# harp_camera_controller.net
KiCad netlist of a schematic drawn in EAGLE
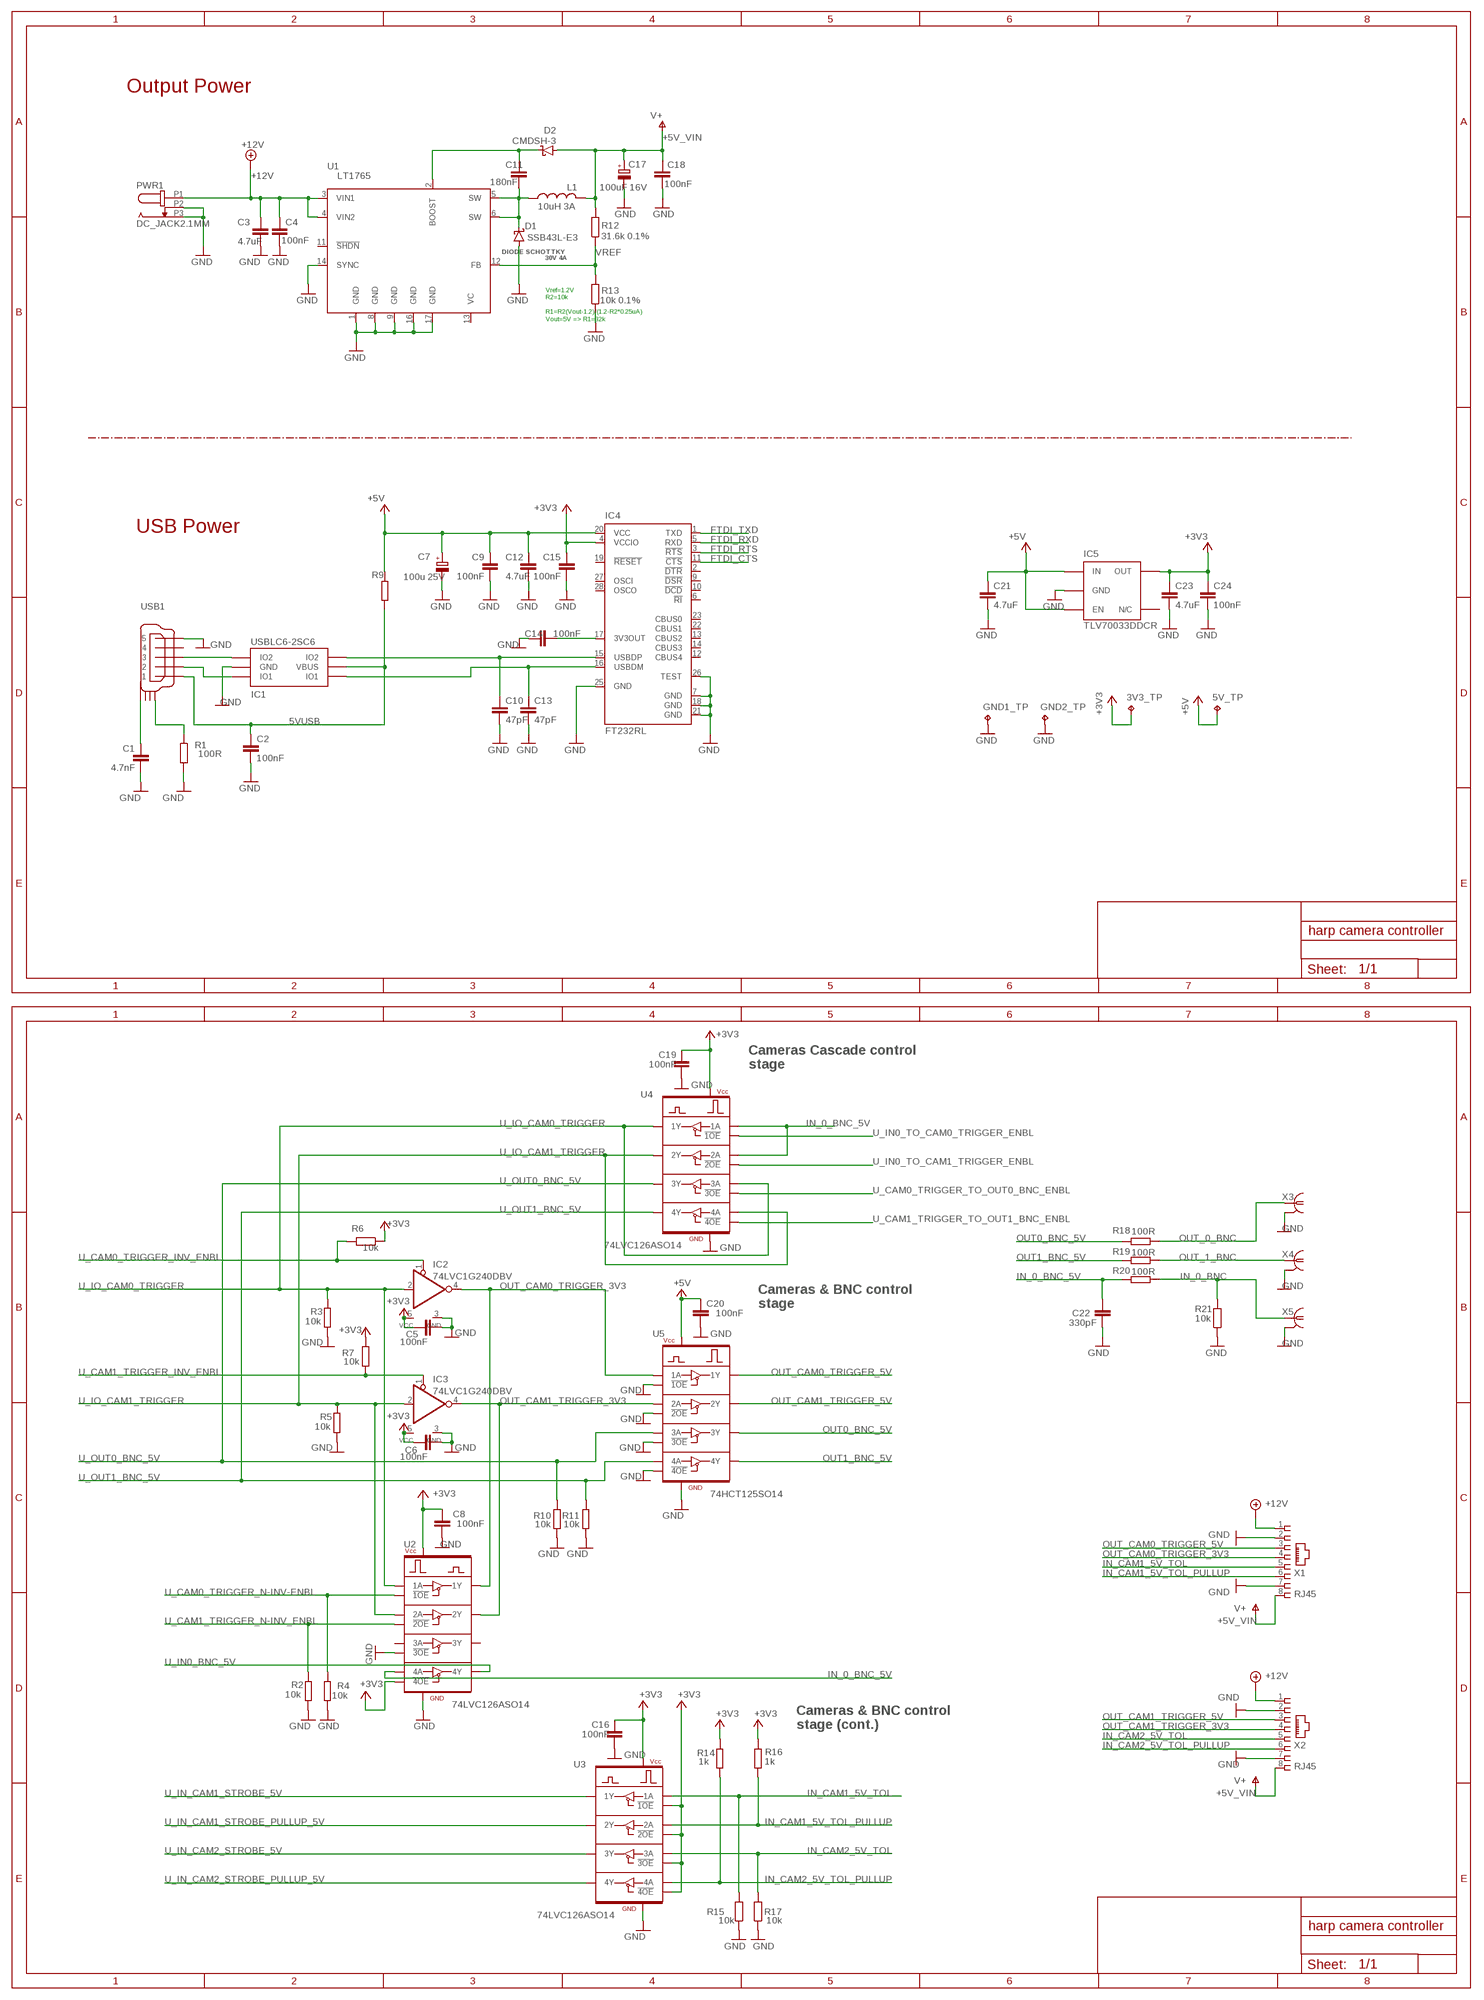
[diagram p0: schematic, sheet 1, part 1 of 2]
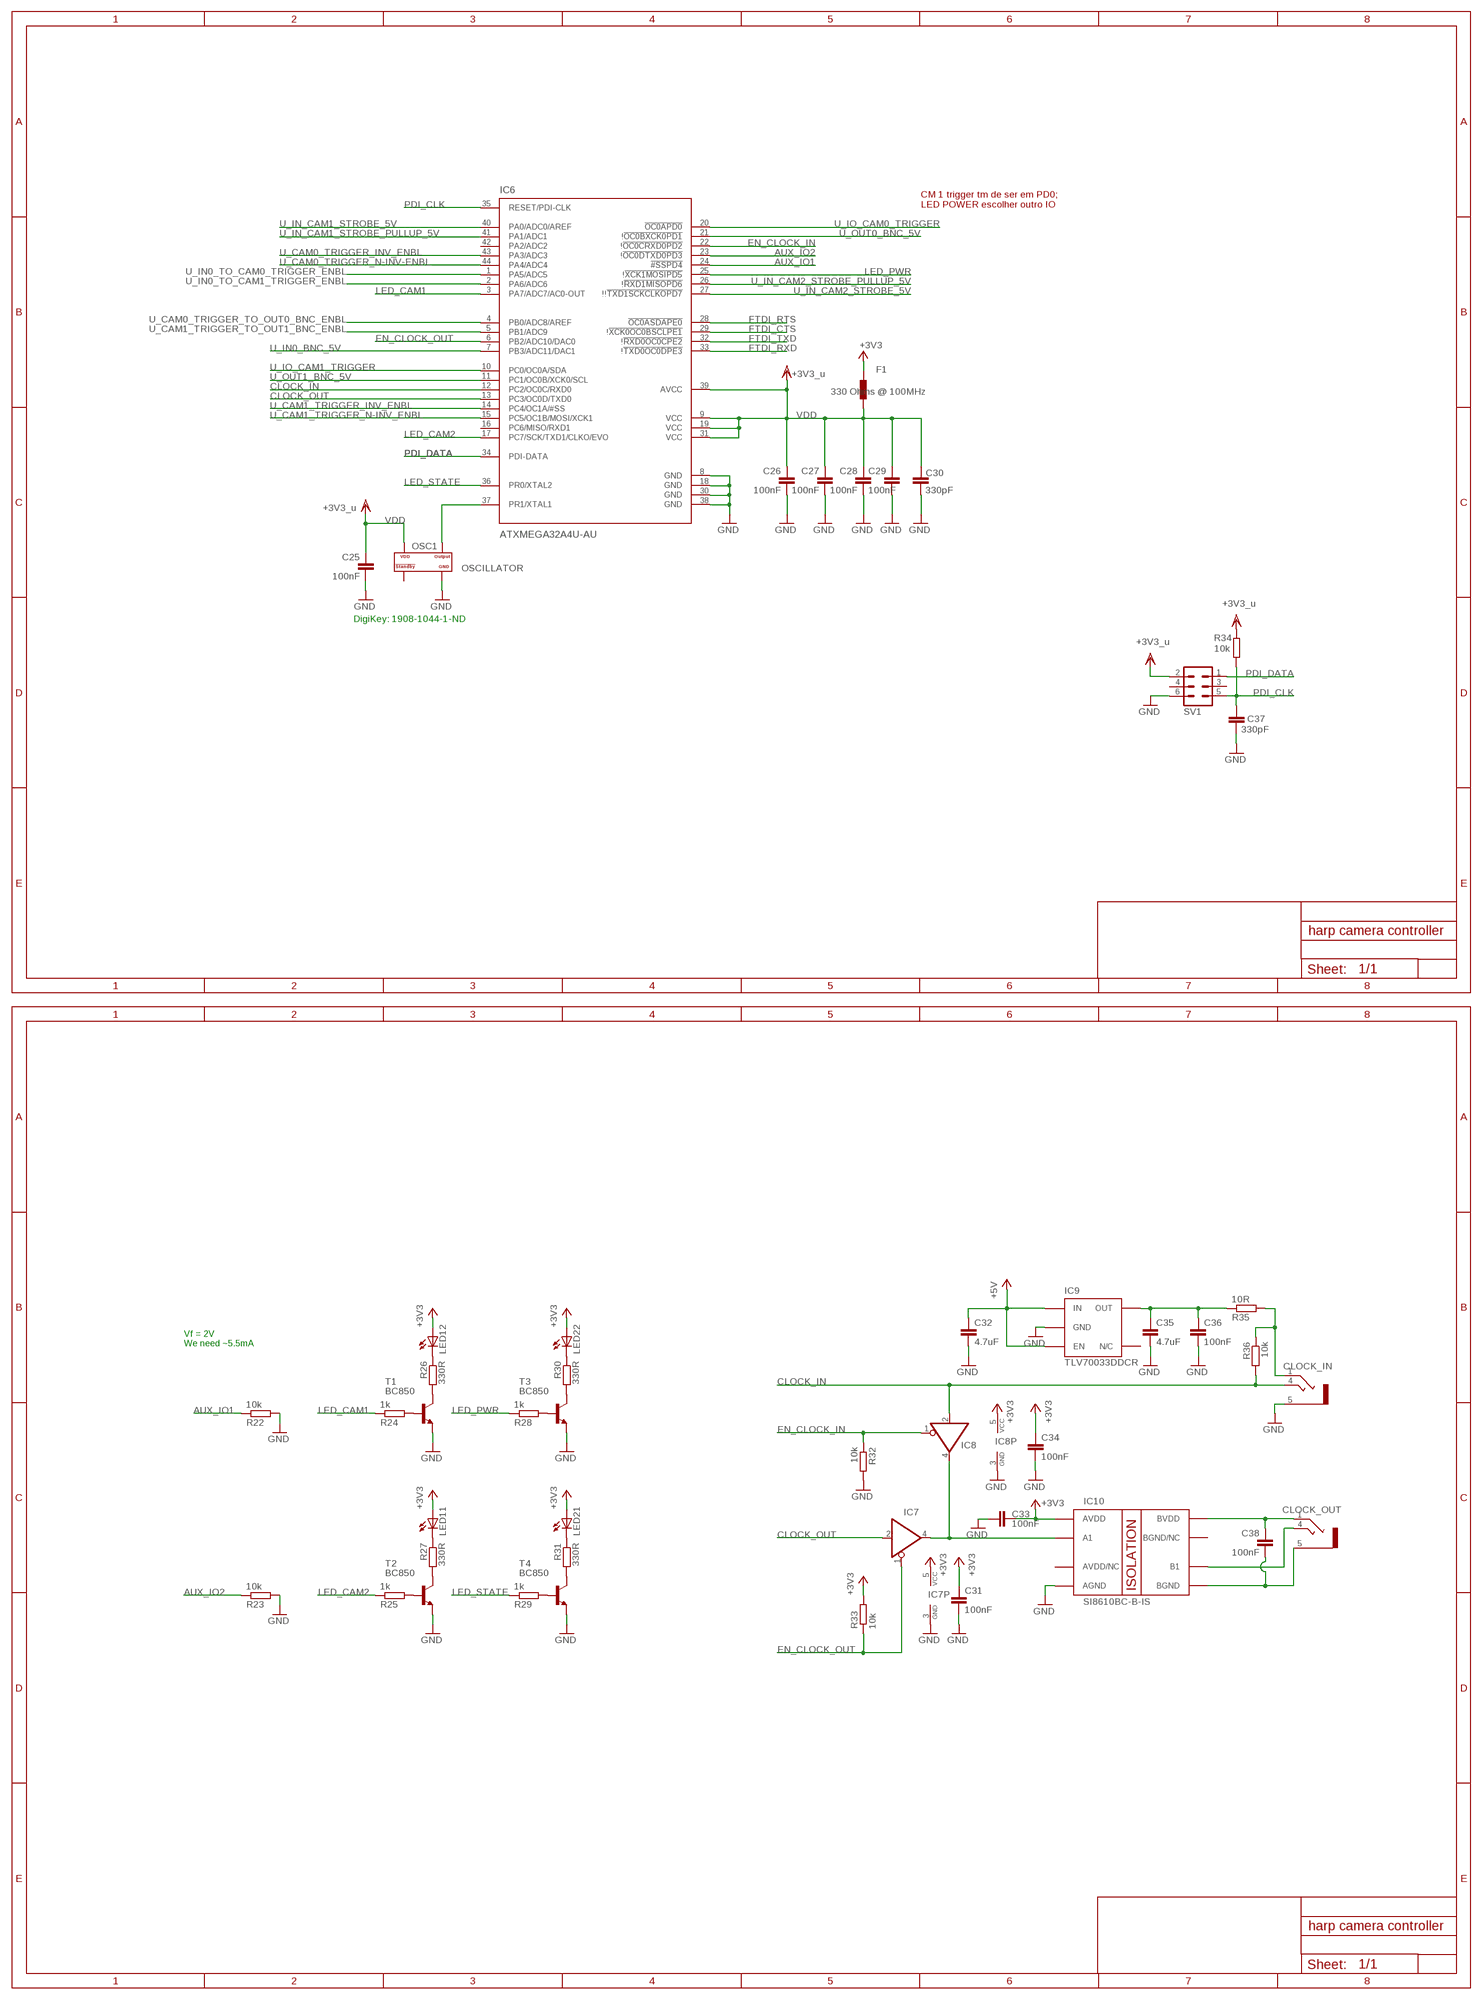
[diagram p1: schematic, sheet 1, part 2 of 2]

(export (version "E")
  (design (tool "Eeschema 10.0.6"))
  (components
    (comp (ref "3V3_TP")
      (value "TPPAD1-13")
      (footprint "eagle-import:P1-13")
      (fields (field (name "MPN") "N.A."))
      (libsource (lib "eagle-import") (part "TPPAD1-13"))
    )
    (comp (ref "5V_TP")
      (value "TPPAD1-13")
      (footprint "eagle-import:P1-13")
      (fields (field (name "MPN") "N.A."))
      (libsource (lib "eagle-import") (part "TPPAD1-13"))
    )
    (comp (ref "C1")
      (value "4.7nF")
      (footprint "eagle-import:C0402")
      (fields (field (name "MPN") "885012205084  "))
      (libsource (lib "eagle-import") (part "C-EUC0402"))
    )
    (comp (ref "C2")
      (value "100nF")
      (footprint "eagle-import:C0402")
      (fields (field (name "MPN") "C1005X7R1H104K050BB"))
      (libsource (lib "eagle-import") (part "C-EUC0402"))
    )
    (comp (ref "C3")
      (value "4.7uF")
      (footprint "eagle-import:C0805")
      (fields (field (name "MPN") "CL21A475KLCLQNC"))
      (libsource (lib "eagle-import") (part "C-EUC0805"))
    )
    (comp (ref "C4")
      (value "100nF")
      (footprint "eagle-import:C0402")
      (fields (field (name "MPN") "C1005X7R1H104K050BB"))
      (libsource (lib "eagle-import") (part "C-EUC0402"))
    )
    (comp (ref "C5")
      (value "100nF")
      (footprint "eagle-import:C0402")
      (fields (field (name "MPN") "C1005X7R1H104K050BB"))
      (libsource (lib "eagle-import") (part "C-EUC0402"))
    )
    (comp (ref "C6")
      (value "100nF")
      (footprint "eagle-import:C0402")
      (fields (field (name "MPN") "C1005X7R1H104K050BB"))
      (libsource (lib "eagle-import") (part "C-EUC0402"))
    )
    (comp (ref "C7")
      (value "100u 25V")
      (footprint "eagle-import:TT2D6")
      (fields (field (name "MPN") "EEU-FM1E101B"))
      (libsource (lib "eagle-import") (part "CPOL-EUTT2D6"))
    )
    (comp (ref "C8")
      (value "100nF")
      (footprint "eagle-import:C0402")
      (fields (field (name "MPN") "C1005X7R1H104K050BB"))
      (libsource (lib "eagle-import") (part "C-EUC0402"))
    )
    (comp (ref "C9")
      (value "100nF")
      (footprint "eagle-import:C0402")
      (fields (field (name "MPN") "C1005X7R1H104K050BB"))
      (libsource (lib "eagle-import") (part "C-EUC0402"))
    )
    (comp (ref "C10")
      (value "47pF")
      (footprint "eagle-import:C0402")
      (fields (field (name "MPN") "04025A470JAT2A"))
      (libsource (lib "eagle-import") (part "C-EUC0402"))
    )
    (comp (ref "C11")
      (value "180nF")
      (footprint "eagle-import:C0603")
      (fields (field (name "MPN") "GCG188R91H184KA01D"))
      (libsource (lib "eagle-import") (part "C-EUC0603"))
    )
    (comp (ref "C12")
      (value "4.7uF")
      (footprint "eagle-import:C0603")
      (fields (field (name "MPN") "C1608X6S1C475K080AC"))
      (libsource (lib "eagle-import") (part "C-EUC0603"))
    )
    (comp (ref "C13")
      (value "47pF")
      (footprint "eagle-import:C0402")
      (fields (field (name "MPN") "04025A470JAT2A"))
      (libsource (lib "eagle-import") (part "C-EUC0402"))
    )
    (comp (ref "C14")
      (value "100nF")
      (footprint "eagle-import:C0402")
      (fields (field (name "MPN") "C1005X7R1H104K050BB"))
      (libsource (lib "eagle-import") (part "C-EUC0402"))
    )
    (comp (ref "C15")
      (value "100nF")
      (footprint "eagle-import:C0402")
      (fields (field (name "MPN") "C1005X7R1H104K050BB"))
      (libsource (lib "eagle-import") (part "C-EUC0402"))
    )
    (comp (ref "C16")
      (value "100nF")
      (footprint "eagle-import:C0402")
      (fields (field (name "MPN") "C1005X7R1H104K050BB"))
      (libsource (lib "eagle-import") (part "C-EUC0402"))
    )
    (comp (ref "C17")
      (value "100uF 16V")
      (footprint "eagle-import:CT7343")
      (fields (field (name "MPN") "T491D107K016AT7280"))
      (libsource (lib "eagle-import") (part "CPOL-EUCT7343"))
    )
    (comp (ref "C18")
      (value "100nF")
      (footprint "eagle-import:C0402")
      (fields (field (name "MPN") "C1005X7R1H104K050BB"))
      (libsource (lib "eagle-import") (part "C-EUC0402"))
    )
    (comp (ref "C19")
      (value "100nF")
      (footprint "eagle-import:C0402")
      (fields (field (name "MPN") "C1005X7R1H104K050BB"))
      (libsource (lib "eagle-import") (part "C-EUC0402"))
    )
    (comp (ref "C20")
      (value "100nF")
      (footprint "eagle-import:C0402")
      (fields (field (name "MPN") "C1005X7R1H104K050BB"))
      (libsource (lib "eagle-import") (part "C-EUC0402"))
    )
    (comp (ref "C21")
      (value "4.7uF")
      (footprint "eagle-import:C0603")
      (fields (field (name "MPN") "C1608X6S1C475K080AC"))
      (libsource (lib "eagle-import") (part "C-EUC0603"))
    )
    (comp (ref "C22")
      (value "330pF")
      (footprint "eagle-import:C0402")
      (fields (field (name "MPN") "C0402C331J5GACTU"))
      (libsource (lib "eagle-import") (part "C-EUC0402"))
    )
    (comp (ref "C23")
      (value "4.7uF")
      (footprint "eagle-import:C0603")
      (fields (field (name "MPN") "C1608X6S1C475K080AC"))
      (libsource (lib "eagle-import") (part "C-EUC0603"))
    )
    (comp (ref "C24")
      (value "100nF")
      (footprint "eagle-import:C0402")
      (fields (field (name "MPN") "C1005X7R1H104K050BB"))
      (libsource (lib "eagle-import") (part "C-EUC0402"))
    )
    (comp (ref "C25")
      (value "100nF")
      (footprint "eagle-import:C0402")
      (fields (field (name "MPN") "C1005X7R1H104K050BB"))
      (libsource (lib "eagle-import") (part "C-EUC0402"))
    )
    (comp (ref "C26")
      (value "100nF")
      (footprint "eagle-import:C0402")
      (fields (field (name "MPN") "C1005X7R1H104K050BB"))
      (libsource (lib "eagle-import") (part "C-EUC0402"))
    )
    (comp (ref "C27")
      (value "100nF")
      (footprint "eagle-import:C0402")
      (fields (field (name "MPN") "C1005X7R1H104K050BB"))
      (libsource (lib "eagle-import") (part "C-EUC0402"))
    )
    (comp (ref "C28")
      (value "100nF")
      (footprint "eagle-import:C0402")
      (fields (field (name "MPN") "C1005X7R1H104K050BB"))
      (libsource (lib "eagle-import") (part "C-EUC0402"))
    )
    (comp (ref "C29")
      (value "100nF")
      (footprint "eagle-import:C0402")
      (fields (field (name "MPN") "C1005X7R1H104K050BB"))
      (libsource (lib "eagle-import") (part "C-EUC0402"))
    )
    (comp (ref "C30")
      (value "330pF")
      (footprint "eagle-import:C0402")
      (fields (field (name "MPN") "C0402C331J5GACTU"))
      (libsource (lib "eagle-import") (part "C-EUC0402"))
    )
    (comp (ref "C31")
      (value "100nF")
      (footprint "eagle-import:C0402")
      (fields (field (name "MPN") "C1005X7R1H104K050BB"))
      (libsource (lib "eagle-import") (part "C-EUC0402"))
    )
    (comp (ref "C32")
      (value "4.7uF")
      (footprint "eagle-import:C0603")
      (fields (field (name "MPN") "C1608X6S1C475K080AC"))
      (libsource (lib "eagle-import") (part "C-EUC0603"))
    )
    (comp (ref "C33")
      (value "100nF")
      (footprint "eagle-import:C0402")
      (fields (field (name "MPN") "C1005X7R1H104K050BB"))
      (libsource (lib "eagle-import") (part "C-EUC0402"))
    )
    (comp (ref "C34")
      (value "100nF")
      (footprint "eagle-import:C0402")
      (fields (field (name "MPN") "C1005X7R1H104K050BB"))
      (libsource (lib "eagle-import") (part "C-EUC0402"))
    )
    (comp (ref "C35")
      (value "4.7uF")
      (footprint "eagle-import:C0603")
      (fields (field (name "MPN") "C1608X6S1C475K080AC"))
      (libsource (lib "eagle-import") (part "C-EUC0603"))
    )
    (comp (ref "C36")
      (value "100nF")
      (footprint "eagle-import:C0402")
      (fields (field (name "MPN") "C1005X7R1H104K050BB"))
      (libsource (lib "eagle-import") (part "C-EUC0402"))
    )
    (comp (ref "C37")
      (value "330pF")
      (footprint "eagle-import:C0402")
      (fields (field (name "MPN") "C0402C331J5GACTU"))
      (libsource (lib "eagle-import") (part "C-EUC0402"))
    )
    (comp (ref "C38")
      (value "100nF")
      (footprint "eagle-import:C0402")
      (fields (field (name "MPN") "C1005X7R1H104K050BB"))
      (libsource (lib "eagle-import") (part "C-EUC0402"))
    )
    (comp (ref "CLOCK_IN")
      (value "CLCK_JACK")
      (footprint "eagle-import:35RASMT2BHNTRX")
      (fields (field (name "MPN") "35RASMT2BHNTRX"))
      (libsource (lib "eagle-import") (part "STEREO_JACK"))
    )
    (comp (ref "CLOCK_OUT")
      (value "CLCK_JACK")
      (footprint "eagle-import:35RASMT2BHNTRX")
      (fields (field (name "MPN") "35RASMT2BHNTRX"))
      (libsource (lib "eagle-import") (part "STEREO_JACK"))
    )
    (comp (ref "D1")
      (value "SSB43L-E3")
      (footprint "eagle-import:SMB")
      (fields (field (name "MPN") "SSB43L-E3/52T"))
      (libsource (lib "eagle-import") (part "SCHOTTKY-DIODE"))
    )
    (comp (ref "D2")
      (value "CMDSH-3")
      (footprint "eagle-import:SOD323-R")
      (libsource (lib "eagle-import") (part "SCHOTTKY-DIODESOD323"))
    )
    (comp (ref "F1")
      (value "330 Ohms @ 100MHz")
      (footprint "eagle-import:R0603")
      (fields (field (name "MPN") "BLM18SG331TN1D"))
      (libsource (lib "eagle-import") (part "BLM15HF0603"))
    )
    (comp (ref "GND1_TP")
      (value "TPPAD1-13")
      (footprint "eagle-import:P1-13")
      (fields (field (name "MPN") "N.A."))
      (libsource (lib "eagle-import") (part "TPPAD1-13"))
    )
    (comp (ref "GND2_TP")
      (value "TPPAD1-13")
      (footprint "eagle-import:P1-13")
      (fields (field (name "MPN") "N.A."))
      (libsource (lib "eagle-import") (part "TPPAD1-13"))
    )
    (comp (ref "IC1")
      (value "USBLC6-2SC6")
      (footprint "eagle-import:SOT23-6L")
      (libsource (lib "eagle-import") (part "USBLC6-2"))
    )
    (comp (ref "IC2")
      (value "74LVC1G240DBV")
      (footprint "eagle-import:SOT23-5")
      (fields (field (name "MPN") "SN74LVC1G240DBVR"))
      (libsource (lib "eagle-import") (part "74LVC1G240DBV"))
    )
    (comp (ref "IC3")
      (value "74LVC1G240DBV")
      (footprint "eagle-import:SOT23-5")
      (fields (field (name "MPN") "SN74LVC1G240DBVR"))
      (libsource (lib "eagle-import") (part "74LVC1G240DBV"))
    )
    (comp (ref "IC4")
      (value "FT232RL")
      (footprint "eagle-import:SSOP28")
      (fields (field (name "MPN") "FT232RL-REEL"))
      (libsource (lib "eagle-import") (part "FT232RL"))
    )
    (comp (ref "IC5")
      (value "TLV70033DDCR")
      (footprint "eagle-import:TSOT23-5")
      (libsource (lib "eagle-import") (part "TLV700XX"))
    )
    (comp (ref "IC6")
      (value "ATXMEGA32A4U-AU")
      (footprint "eagle-import:QFP80P1200X1200X120-44N")
      (fields (field (name "MPN") "ATXMEGA32A4U-AUR"))
      (libsource (lib "eagle-import") (part "AT-XMEGA-XXA4-AU"))
    )
    (comp (ref "IC7")
      (value "SN74LVC1G125DBVT")
      (footprint "eagle-import:SOT23-5")
      (fields
        (field (name "DIGIKEY_PN") "296-26595-1-ND")
        (field (name "MOUSER_PN") "595-SN74LVC1G125DBVT")
        (field (name "MPN") "SN74LVC1G125DBVT")
      )
      (libsource (lib "eagle-import") (part "741G125DBVAHC"))
    )
    (comp (ref "IC8")
      (value "SN74LVC1G125DBVT")
      (footprint "eagle-import:SOT23-5")
      (fields
        (field (name "DIGIKEY_PN") "296-26595-1-ND")
        (field (name "MOUSER_PN") "595-SN74LVC1G125DBVT")
        (field (name "MPN") "SN74LVC1G125DBVT")
      )
      (libsource (lib "eagle-import") (part "741G125DBVAHC"))
    )
    (comp (ref "IC9")
      (value "TLV70033DDCR")
      (footprint "eagle-import:TSOT23-5")
      (libsource (lib "eagle-import") (part "TLV700XX"))
    )
    (comp (ref "IC10")
      (value "SI8610BC-B-IS")
      (footprint "eagle-import:SO-08")
      (fields (field (name "MPN") "SI8610EC-B-IS"))
      (libsource (lib "eagle-import") (part "SI8610"))
    )
    (comp (ref "L1")
      (value "10uH 3A")
      (footprint "eagle-import:L_IHLP_PADS")
      (fields (field (name "MPN") "IHLP2525CZER100M01"))
      (libsource (lib "eagle-import") (part "L_IHLP2525CZER100M01"))
    )
    (comp (ref "LED1")
      (value "RED_LEDs")
      (footprint "eagle-import:569-011X-X00_LED_ARRAY")
      (fields (field (name "MPN") "5690-111-100F"))
      (libsource (lib "eagle-import") (part "LED_2X_VERTICAL"))
    )
    (comp (ref "LED2")
      (value "RED_LEDs")
      (footprint "eagle-import:569-011X-X00_LED_ARRAY")
      (fields (field (name "MPN") "5690-111-100F"))
      (libsource (lib "eagle-import") (part "LED_2X_VERTICAL"))
    )
    (comp (ref "OSC1")
      (value "OSCILLATOR")
      (footprint "eagle-import:OSCILLATOR_3.2X2.5")
      (fields (field (name "MPN") "O 32,0-JT32C-A-K-3,3-LF"))
      (libsource (lib "eagle-import") (part "OSCILLATOR"))
    )
    (comp (ref "PWR1")
      (value "DC_JACK2.1MM")
      (footprint "eagle-import:DC_POWER_INPUT_2.1MM")
      (fields (field (name "MPN") "163-179PH-EX"))
      (libsource (lib "eagle-import") (part "DC_JACK2.1MM"))
    )
    (comp (ref "R1")
      (value "100R")
      (footprint "eagle-import:R0603")
      (fields (field (name "MPN") "ERJ-3EKF1000V"))
      (libsource (lib "eagle-import") (part "R-EU_R0603"))
    )
    (comp (ref "R2")
      (value "10k")
      (footprint "eagle-import:R0402")
      (fields (field (name "MPN") "CRCW040210K0FKED"))
      (libsource (lib "eagle-import") (part "R-EU_R0402"))
    )
    (comp (ref "R3")
      (value "10k")
      (footprint "eagle-import:R0402")
      (fields (field (name "MPN") "CRCW040210K0FKED"))
      (libsource (lib "eagle-import") (part "R-EU_R0402"))
    )
    (comp (ref "R4")
      (value "10k")
      (footprint "eagle-import:R0402")
      (fields (field (name "MPN") "CRCW040210K0FKED"))
      (libsource (lib "eagle-import") (part "R-EU_R0402"))
    )
    (comp (ref "R5")
      (value "10k")
      (footprint "eagle-import:R0402")
      (fields (field (name "MPN") "CRCW040210K0FKED"))
      (libsource (lib "eagle-import") (part "R-EU_R0402"))
    )
    (comp (ref "R6")
      (value "10k")
      (footprint "eagle-import:R0402")
      (fields (field (name "MPN") "CRCW040210K0FKED"))
      (libsource (lib "eagle-import") (part "R-EU_R0402"))
    )
    (comp (ref "R7")
      (value "10k")
      (footprint "eagle-import:R0402")
      (fields (field (name "MPN") "CRCW040210K0FKED"))
      (libsource (lib "eagle-import") (part "R-EU_R0402"))
    )
    (comp (ref "R9")
      (value "40R@100MHz")
      (footprint "eagle-import:R0805")
      (fields (field (name "MPN") "MI0805K400R-10"))
      (libsource (lib "eagle-import") (part "R-EU_R0805"))
    )
    (comp (ref "R10")
      (value "10k")
      (footprint "eagle-import:R0402")
      (fields (field (name "MPN") "CRCW040210K0FKED"))
      (libsource (lib "eagle-import") (part "R-EU_R0402"))
    )
    (comp (ref "R11")
      (value "10k")
      (footprint "eagle-import:R0402")
      (fields (field (name "MPN") "CRCW040210K0FKED"))
      (libsource (lib "eagle-import") (part "R-EU_R0402"))
    )
    (comp (ref "R12")
      (value "31.6k 0.1%")
      (footprint "eagle-import:R0402")
      (fields (field (name "MPN") "RC0402FR-0740K2L"))
      (libsource (lib "eagle-import") (part "R-EU_R0402"))
    )
    (comp (ref "R13")
      (value "10k 0.1%")
      (footprint "eagle-import:R0402")
      (fields (field (name "MPN") "CRCW040210K0FKED"))
      (libsource (lib "eagle-import") (part "R-EU_R0402"))
    )
    (comp (ref "R14")
      (value "1k")
      (footprint "eagle-import:R0402")
      (fields (field (name "MPN") "CRCW04021K00FKEDC"))
      (libsource (lib "eagle-import") (part "R-EU_R0402"))
    )
    (comp (ref "R15")
      (value "10k")
      (footprint "eagle-import:R0402")
      (fields (field (name "MPN") "CRCW040210K0FKED"))
      (libsource (lib "eagle-import") (part "R-EU_R0402"))
    )
    (comp (ref "R16")
      (value "1k")
      (footprint "eagle-import:R0402")
      (fields (field (name "MPN") "CRCW04021K00FKEDC"))
      (libsource (lib "eagle-import") (part "R-EU_R0402"))
    )
    (comp (ref "R17")
      (value "10k")
      (footprint "eagle-import:R0402")
      (fields (field (name "MPN") "CRCW040210K0FKED"))
      (libsource (lib "eagle-import") (part "R-EU_R0402"))
    )
    (comp (ref "R18")
      (value "100R")
      (footprint "eagle-import:R0603")
      (fields (field (name "MPN") "ERJ-3EKF1000V"))
      (libsource (lib "eagle-import") (part "R-EU_R0603"))
    )
    (comp (ref "R19")
      (value "100R")
      (footprint "eagle-import:R0603")
      (fields (field (name "MPN") "ERJ-3EKF1000V"))
      (libsource (lib "eagle-import") (part "R-EU_R0603"))
    )
    (comp (ref "R20")
      (value "100R")
      (footprint "eagle-import:R0603")
      (fields (field (name "MPN") "ERJ-3EKF1000V"))
      (libsource (lib "eagle-import") (part "R-EU_R0603"))
    )
    (comp (ref "R21")
      (value "10k")
      (footprint "eagle-import:R0402")
      (fields (field (name "MPN") "CRCW040210K0FKED"))
      (libsource (lib "eagle-import") (part "R-EU_R0402"))
    )
    (comp (ref "R22")
      (value "10k")
      (footprint "eagle-import:R0402")
      (fields (field (name "MPN") "CRCW040210K0FKED"))
      (libsource (lib "eagle-import") (part "R-EU_R0402"))
    )
    (comp (ref "R23")
      (value "10k")
      (footprint "eagle-import:R0402")
      (fields (field (name "MPN") "CRCW040210K0FKED"))
      (libsource (lib "eagle-import") (part "R-EU_R0402"))
    )
    (comp (ref "R24")
      (value "1k")
      (footprint "eagle-import:R0402")
      (fields (field (name "MPN") "CRCW04021K00FKEDC"))
      (libsource (lib "eagle-import") (part "R-EU_R0402"))
    )
    (comp (ref "R25")
      (value "1k")
      (footprint "eagle-import:R0402")
      (fields (field (name "MPN") "CRCW04021K00FKEDC"))
      (libsource (lib "eagle-import") (part "R-EU_R0402"))
    )
    (comp (ref "R26")
      (value "330R")
      (footprint "eagle-import:R0402")
      (fields (field (name "MPN") "RC0402FR-07330RL "))
      (libsource (lib "eagle-import") (part "R-EU_R0402"))
    )
    (comp (ref "R27")
      (value "330R")
      (footprint "eagle-import:R0402")
      (fields (field (name "MPN") "RC0402FR-07330RL "))
      (libsource (lib "eagle-import") (part "R-EU_R0402"))
    )
    (comp (ref "R28")
      (value "1k")
      (footprint "eagle-import:R0402")
      (fields (field (name "MPN") "CRCW04021K00FKEDC"))
      (libsource (lib "eagle-import") (part "R-EU_R0402"))
    )
    (comp (ref "R29")
      (value "1k")
      (footprint "eagle-import:R0402")
      (fields (field (name "MPN") "CRCW04021K00FKEDC"))
      (libsource (lib "eagle-import") (part "R-EU_R0402"))
    )
    (comp (ref "R30")
      (value "330R")
      (footprint "eagle-import:R0402")
      (fields (field (name "MPN") "RC0402FR-07330RL "))
      (libsource (lib "eagle-import") (part "R-EU_R0402"))
    )
    (comp (ref "R31")
      (value "330R")
      (footprint "eagle-import:R0402")
      (fields (field (name "MPN") "RC0402FR-07330RL "))
      (libsource (lib "eagle-import") (part "R-EU_R0402"))
    )
    (comp (ref "R32")
      (value "10k")
      (footprint "eagle-import:R0402")
      (fields (field (name "MPN") "CRCW040210K0FKED"))
      (libsource (lib "eagle-import") (part "R-EU_R0402"))
    )
    (comp (ref "R33")
      (value "10k")
      (footprint "eagle-import:R0402")
      (fields (field (name "MPN") "CRCW040210K0FKED"))
      (libsource (lib "eagle-import") (part "R-EU_R0402"))
    )
    (comp (ref "R34")
      (value "10k")
      (footprint "eagle-import:R0402")
      (fields (field (name "MPN") "CRCW040210K0FKED"))
      (libsource (lib "eagle-import") (part "R-EU_R0402"))
    )
    (comp (ref "R35")
      (value "10R")
      (footprint "eagle-import:R0402")
      (fields (field (name "MPN") "CRCW040210R0FKEDC"))
      (libsource (lib "eagle-import") (part "R-EU_R0402"))
    )
    (comp (ref "R36")
      (value "10k")
      (footprint "eagle-import:R0402")
      (fields (field (name "MPN") "CRCW040210K0FKED"))
      (libsource (lib "eagle-import") (part "R-EU_R0402"))
    )
    (comp (ref "SV1")
      (value "PROG HEADER")
      (footprint "eagle-import:MA03-2")
      (fields (field (name "MPN") "61300621121"))
      (libsource (lib "eagle-import") (part "MA03-2"))
    )
    (comp (ref "T1")
      (value "BC850")
      (footprint "eagle-import:SOT23")
      (fields (field (name "MPN") "BC850C,215"))
      (libsource (lib "eagle-import") (part "BC850"))
    )
    (comp (ref "T2")
      (value "BC850")
      (footprint "eagle-import:SOT23")
      (fields (field (name "MPN") "BC850C,215"))
      (libsource (lib "eagle-import") (part "BC850"))
    )
    (comp (ref "T3")
      (value "BC850")
      (footprint "eagle-import:SOT23")
      (fields (field (name "MPN") "BC850C,215"))
      (libsource (lib "eagle-import") (part "BC850"))
    )
    (comp (ref "T4")
      (value "BC850")
      (footprint "eagle-import:SOT23")
      (fields (field (name "MPN") "BC850C,215"))
      (libsource (lib "eagle-import") (part "BC850"))
    )
    (comp (ref "U1")
      (value "LT1765")
      (footprint "eagle-import:TSSOP16EXP")
      (fields (field (name "MPN") "LT1765EFE#PBF"))
      (libsource (lib "eagle-import") (part "LT1765"))
    )
    (comp (ref "U2")
      (value "74LVC126ASO14")
      (footprint "eagle-import:SO14")
      (fields (field (name "MPN") "74LVC126AD,118  "))
      (libsource (lib "eagle-import") (part "74LVC126ASO14"))
    )
    (comp (ref "U3")
      (value "74LVC126ASO14")
      (footprint "eagle-import:SO14")
      (fields (field (name "MPN") "74LVC126AD,118  "))
      (libsource (lib "eagle-import") (part "74LVC126ASO14"))
    )
    (comp (ref "U4")
      (value "74LVC126ASO14")
      (footprint "eagle-import:SO14")
      (fields (field (name "MPN") "74LVC126AD,118  "))
      (libsource (lib "eagle-import") (part "74LVC126ASO14"))
    )
    (comp (ref "U5")
      (value "74HCT125SO14")
      (footprint "eagle-import:SO14")
      (fields (field (name "MPN") "74HCT125D,653"))
      (libsource (lib "eagle-import") (part "74HCT125SO14"))
    )
    (comp (ref "USB1")
      (value "mini USB")
      (footprint "eagle-import:240-0002-1")
      (fields (field (name "MPN") "UX60-MB-5S8 "))
      (libsource (lib "eagle-import") (part "USB_MINI_B"))
    )
    (comp (ref "X1")
      (value "RJ45")
      (footprint "eagle-import:RJ45-NO-SHIELD")
      (fields (field (name "MPN") "215877-1"))
      (libsource (lib "eagle-import") (part "RJ45"))
    )
    (comp (ref "X2")
      (value "RJ45")
      (footprint "eagle-import:RJ45-NO-SHIELD")
      (fields (field (name "MPN") "215877-1"))
      (libsource (lib "eagle-import") (part "RJ45"))
    )
    (comp (ref "X3")
      (value "BNC plug")
      (footprint "eagle-import:0731000105")
      (fields (field (name "MPN") "73100-0105"))
      (libsource (lib "eagle-import") (part "BNC_0731000105"))
    )
    (comp (ref "X4")
      (value "BNC plug")
      (footprint "eagle-import:0731000105")
      (fields (field (name "MPN") "73100-0105"))
      (libsource (lib "eagle-import") (part "BNC_0731000105"))
    )
    (comp (ref "X5")
      (value "BNC plug")
      (footprint "eagle-import:0731000105")
      (fields (field (name "MPN") "73100-0105"))
      (libsource (lib "eagle-import") (part "BNC_0731000105"))
    )
  )
  (nets
    (net (code "1") (name "+3V3") (class "Default")
      (node (ref "3V3_TP") (pin "TP") (pinfunction "TP_TP") (pintype "input"))
      (node (ref "C15") (pin "1") (pinfunction "1_1") (pintype "passive"))
      (node (ref "C16") (pin "1") (pinfunction "1_1") (pintype "passive"))
      (node (ref "C19") (pin "1") (pinfunction "1_1") (pintype "passive"))
      (node (ref "C23") (pin "1") (pinfunction "1_1") (pintype "passive"))
      (node (ref "C24") (pin "1") (pinfunction "1_1") (pintype "passive"))
      (node (ref "C31") (pin "1") (pinfunction "1_1") (pintype "passive"))
      (node (ref "C33") (pin "1") (pinfunction "1_1") (pintype "passive"))
      (node (ref "C34") (pin "1") (pinfunction "1_1") (pintype "passive"))
      (node (ref "C5") (pin "1") (pinfunction "1_1") (pintype "passive"))
      (node (ref "C6") (pin "1") (pinfunction "1_1") (pintype "passive"))
      (node (ref "C8") (pin "1") (pinfunction "1_1") (pintype "passive"))
      (node (ref "F1") (pin "2") (pinfunction "2_2") (pintype "passive"))
      (node (ref "IC10") (pin "1") (pinfunction "AVDD_1") (pintype "bidirectional"))
      (node (ref "IC2") (pin "5") (pinfunction "VCC_5") (pintype "input"))
      (node (ref "IC3") (pin "5") (pinfunction "VCC_5") (pintype "input"))
      (node (ref "IC4") (pin "4") (pinfunction "VCCIO_4") (pintype "input"))
      (node (ref "IC5") (pin "5") (pinfunction "OUT_5") (pintype "bidirectional"))
      (node (ref "IC7") (pin "5") (pinfunction "VCC_5") (pintype "power_in"))
      (node (ref "IC8") (pin "5") (pinfunction "VCC_5") (pintype "power_in"))
      (node (ref "LED1") (pin "A1") (pinfunction "A_A1") (pintype "passive"))
      (node (ref "LED1") (pin "A2") (pinfunction "A_A2") (pintype "passive"))
      (node (ref "LED2") (pin "A1") (pinfunction "A_A1") (pintype "passive"))
      (node (ref "LED2") (pin "A2") (pinfunction "A_A2") (pintype "passive"))
      (node (ref "R14") (pin "1") (pinfunction "1_1") (pintype "passive"))
      (node (ref "R16") (pin "1") (pinfunction "1_1") (pintype "passive"))
      (node (ref "R33") (pin "2") (pinfunction "2_2") (pintype "passive"))
      (node (ref "R6") (pin "1") (pinfunction "1_1") (pintype "passive"))
      (node (ref "R7") (pin "1") (pinfunction "1_1") (pintype "passive"))
      (node (ref "U2") (pin "13") (pinfunction "~{4OE}_13") (pintype "bidirectional"))
      (node (ref "U2") (pin "14") (pinfunction "VCC_14") (pintype "input"))
      (node (ref "U3") (pin "1") (pinfunction "~{1OE}_1") (pintype "bidirectional"))
      (node (ref "U3") (pin "10") (pinfunction "~{3OE}_10") (pintype "bidirectional"))
      (node (ref "U3") (pin "13") (pinfunction "~{4OE}_13") (pintype "bidirectional"))
      (node (ref "U3") (pin "14") (pinfunction "VCC_14") (pintype "input"))
      (node (ref "U3") (pin "4") (pinfunction "~{2OE}_4") (pintype "bidirectional"))
      (node (ref "U4") (pin "14") (pinfunction "VCC_14") (pintype "input"))
    )
    (net (code "2") (name "+3V3_u") (class "Default")
      (node (ref "C25") (pin "1") (pinfunction "1_1") (pintype "passive"))
      (node (ref "C26") (pin "1") (pinfunction "1_1") (pintype "passive"))
      (node (ref "C27") (pin "1") (pinfunction "1_1") (pintype "passive"))
      (node (ref "C28") (pin "1") (pinfunction "1_1") (pintype "passive"))
      (node (ref "C29") (pin "1") (pinfunction "1_1") (pintype "passive"))
      (node (ref "C30") (pin "1") (pinfunction "1_1") (pintype "passive"))
      (node (ref "F1") (pin "1") (pinfunction "1_1") (pintype "passive"))
      (node (ref "IC6") (pin "19") (pinfunction "VCC_19") (pintype "power_in"))
      (node (ref "IC6") (pin "31") (pinfunction "VCC_31") (pintype "power_in"))
      (node (ref "IC6") (pin "39") (pinfunction "AVCC_39") (pintype "power_in"))
      (node (ref "IC6") (pin "9") (pinfunction "VCC_9") (pintype "power_in"))
      (node (ref "OSC1") (pin "P$4") (pinfunction "VDD_P$4") (pintype "passive"))
      (node (ref "R34") (pin "2") (pinfunction "2_2") (pintype "passive"))
      (node (ref "SV1") (pin "2") (pinfunction "2_2") (pintype "passive"))
    )
    (net (code "3") (name "+5V") (class "Default")
      (node (ref "5V_TP") (pin "TP") (pinfunction "TP_TP") (pintype "input"))
      (node (ref "C12") (pin "1") (pinfunction "1_1") (pintype "passive"))
      (node (ref "C20") (pin "1") (pinfunction "1_1") (pintype "passive"))
      (node (ref "C21") (pin "1") (pinfunction "1_1") (pintype "passive"))
      (node (ref "C32") (pin "1") (pinfunction "1_1") (pintype "passive"))
      (node (ref "C7") (pin "+") (pinfunction "+_+") (pintype "passive"))
      (node (ref "C9") (pin "1") (pinfunction "1_1") (pintype "passive"))
      (node (ref "IC4") (pin "20") (pinfunction "VCC_20") (pintype "input"))
      (node (ref "IC5") (pin "1") (pinfunction "IN_1") (pintype "bidirectional"))
      (node (ref "IC5") (pin "3") (pinfunction "EN_3") (pintype "bidirectional"))
      (node (ref "IC9") (pin "1") (pinfunction "IN_1") (pintype "bidirectional"))
      (node (ref "IC9") (pin "3") (pinfunction "EN_3") (pintype "bidirectional"))
      (node (ref "R9") (pin "1") (pinfunction "1_1") (pintype "passive"))
      (node (ref "U5") (pin "14") (pinfunction "VCC_14") (pintype "input"))
    )
    (net (code "4") (name "+12V") (class "Default")
      (node (ref "C3") (pin "1") (pinfunction "1_1") (pintype "passive"))
      (node (ref "C4") (pin "1") (pinfunction "1_1") (pintype "passive"))
      (node (ref "PWR1") (pin "P1") (pinfunction "1_P1") (pintype "passive"))
      (node (ref "U1") (pin "3") (pinfunction "VIN1_3") (pintype "bidirectional"))
      (node (ref "U1") (pin "4") (pinfunction "VIN2_4") (pintype "bidirectional"))
      (node (ref "X1") (pin "1") (pinfunction "1_1") (pintype "passive"))
      (node (ref "X2") (pin "1") (pinfunction "1_1") (pintype "passive"))
    )
    (net (code "5") (name "/5VUSB") (class "Default")
      (node (ref "C2") (pin "1") (pinfunction "1_1") (pintype "passive"))
      (node (ref "IC1") (pin "P$5") (pinfunction "VBUS_P$5") (pintype "bidirectional"))
      (node (ref "R9") (pin "2") (pinfunction "2_2") (pintype "passive"))
      (node (ref "USB1") (pin "P$1") (pinfunction "1_P$1") (pintype "bidirectional"))
    )
    (net (code "6") (name "/AUX_IO1") (class "Default")
      (node (ref "IC6") (pin "24") (pinfunction "~{#SSPD4}_24") (pintype "bidirectional"))
      (node (ref "R22") (pin "1") (pinfunction "1_1") (pintype "passive"))
    )
    (net (code "7") (name "/AUX_IO2") (class "Default")
      (node (ref "IC6") (pin "23") (pinfunction "~OC0DTXD0PD3_23") (pintype "bidirectional"))
      (node (ref "R23") (pin "1") (pinfunction "1_1") (pintype "passive"))
    )
    (net (code "8") (name "/CLOCK_IN") (class "Default")
      (node (ref "CLOCK_IN") (pin "4") (pinfunction "4_4") (pintype "passive"))
      (node (ref "IC6") (pin "12") (pinfunction "PC2/OC0C/RXD0_12") (pintype "bidirectional"))
      (node (ref "IC8") (pin "2") (pinfunction "I_2") (pintype "input"))
      (node (ref "R36") (pin "2") (pinfunction "2_2") (pintype "passive"))
    )
    (net (code "9") (name "/CLOCK_OUT") (class "Default")
      (node (ref "IC6") (pin "13") (pinfunction "PC3/OC0D/TXD0_13") (pintype "bidirectional"))
      (node (ref "IC7") (pin "2") (pinfunction "I_2") (pintype "input"))
    )
    (net (code "10") (name "/EN_CLOCK_IN") (class "Default")
      (node (ref "IC6") (pin "22") (pinfunction "~OC0CRXD0PD2_22") (pintype "bidirectional"))
      (node (ref "IC8") (pin "1") (pinfunction "OE_1") (pintype "input"))
      (node (ref "R32") (pin "1") (pinfunction "1_1") (pintype "passive"))
    )
    (net (code "11") (name "/EN_CLOCK_OUT") (class "Default")
      (node (ref "IC6") (pin "6") (pinfunction "PB2/ADC10/DAC0_6") (pintype "bidirectional"))
      (node (ref "IC7") (pin "1") (pinfunction "OE_1") (pintype "input"))
      (node (ref "R33") (pin "1") (pinfunction "1_1") (pintype "passive"))
    )
    (net (code "12") (name "/FTDI_CTS") (class "Default")
      (node (ref "IC4") (pin "11") (pinfunction "~{CTS}_11") (pintype "input"))
      (node (ref "IC6") (pin "29") (pinfunction "~XCK0OC0BSCLPE1_29") (pintype "bidirectional"))
    )
    (net (code "13") (name "/FTDI_RTS") (class "Default")
      (node (ref "IC4") (pin "3") (pinfunction "~{RTS}_3") (pintype "output"))
      (node (ref "IC6") (pin "28") (pinfunction "~{OC0ASDAPE0}_28") (pintype "bidirectional"))
    )
    (net (code "14") (name "/FTDI_RXD") (class "Default")
      (node (ref "IC4") (pin "5") (pinfunction "RXD_5") (pintype "input"))
      (node (ref "IC6") (pin "33") (pinfunction "~TXD0OC0DPE3_33") (pintype "bidirectional"))
    )
    (net (code "15") (name "/FTDI_TXD") (class "Default")
      (node (ref "IC4") (pin "1") (pinfunction "TXD_1") (pintype "output"))
      (node (ref "IC6") (pin "32") (pinfunction "~RXD0OC0CPE2_32") (pintype "bidirectional"))
    )
    (net (code "16") (name "/IN_0_BNC") (class "Default")
      (node (ref "R20") (pin "1") (pinfunction "1_1") (pintype "passive"))
      (node (ref "R21") (pin "2") (pinfunction "2_2") (pintype "passive"))
      (node (ref "X5") (pin "1") (pinfunction "1_1") (pintype "passive"))
    )
    (net (code "17") (name "/IN_0_BNC_5V") (class "Default")
      (node (ref "C22") (pin "1") (pinfunction "1_1") (pintype "passive"))
      (node (ref "R20") (pin "2") (pinfunction "2_2") (pintype "passive"))
      (node (ref "U2") (pin "12") (pinfunction "4A_12") (pintype "bidirectional"))
      (node (ref "U4") (pin "2") (pinfunction "1A_2") (pintype "bidirectional"))
      (node (ref "U4") (pin "5") (pinfunction "2A_5") (pintype "bidirectional"))
    )
    (net (code "18") (name "/IN_CAM1_5V_TOL") (class "Default")
      (node (ref "R15") (pin "2") (pinfunction "2_2") (pintype "passive"))
      (node (ref "U3") (pin "2") (pinfunction "1A_2") (pintype "bidirectional"))
      (node (ref "X1") (pin "5") (pinfunction "5_5") (pintype "passive"))
    )
    (net (code "19") (name "/IN_CAM1_5V_TOL_PULLUP") (class "Default")
      (node (ref "R16") (pin "2") (pinfunction "2_2") (pintype "passive"))
      (node (ref "U3") (pin "5") (pinfunction "2A_5") (pintype "bidirectional"))
      (node (ref "X1") (pin "6") (pinfunction "6_6") (pintype "passive"))
    )
    (net (code "20") (name "/IN_CAM2_5V_TOL") (class "Default")
      (node (ref "R17") (pin "2") (pinfunction "2_2") (pintype "passive"))
      (node (ref "U3") (pin "9") (pinfunction "3A_9") (pintype "bidirectional"))
      (node (ref "X2") (pin "5") (pinfunction "5_5") (pintype "passive"))
    )
    (net (code "21") (name "/IN_CAM2_5V_TOL_PULLUP") (class "Default")
      (node (ref "R14") (pin "2") (pinfunction "2_2") (pintype "passive"))
      (node (ref "U3") (pin "12") (pinfunction "4A_12") (pintype "bidirectional"))
      (node (ref "X2") (pin "6") (pinfunction "6_6") (pintype "passive"))
    )
    (net (code "22") (name "/LED_CAM1") (class "Default")
      (node (ref "IC6") (pin "3") (pinfunction "PA7/ADC7/AC0-OUT_3") (pintype "bidirectional"))
      (node (ref "R24") (pin "1") (pinfunction "1_1") (pintype "passive"))
    )
    (net (code "23") (name "/LED_CAM2") (class "Default")
      (node (ref "IC6") (pin "17") (pinfunction "PC7/SCK/TXD1/CLKO/EVO_17") (pintype "bidirectional"))
      (node (ref "R25") (pin "1") (pinfunction "1_1") (pintype "passive"))
    )
    (net (code "24") (name "/LED_PWR") (class "Default")
      (node (ref "IC6") (pin "25") (pinfunction "~XCK1MOSIPD5_25") (pintype "bidirectional"))
      (node (ref "R28") (pin "1") (pinfunction "1_1") (pintype "passive"))
    )
    (net (code "25") (name "/LED_STATE") (class "Default")
      (node (ref "IC6") (pin "36") (pinfunction "PR0/XTAL2_36") (pintype "bidirectional"))
      (node (ref "R29") (pin "1") (pinfunction "1_1") (pintype "passive"))
    )
    (net (code "26") (name "/OUT0_BNC_5V") (class "Default")
      (node (ref "R18") (pin "2") (pinfunction "2_2") (pintype "passive"))
      (node (ref "U5") (pin "8") (pinfunction "3Y_8") (pintype "bidirectional"))
    )
    (net (code "27") (name "/OUT1_BNC_5V") (class "Default")
      (node (ref "R19") (pin "2") (pinfunction "2_2") (pintype "passive"))
      (node (ref "U5") (pin "11") (pinfunction "4Y_11") (pintype "bidirectional"))
    )
    (net (code "28") (name "/OUT_0_BNC") (class "Default")
      (node (ref "R18") (pin "1") (pinfunction "1_1") (pintype "passive"))
      (node (ref "X3") (pin "1") (pinfunction "1_1") (pintype "passive"))
    )
    (net (code "29") (name "/OUT_1_BNC") (class "Default")
      (node (ref "R19") (pin "1") (pinfunction "1_1") (pintype "passive"))
      (node (ref "X4") (pin "1") (pinfunction "1_1") (pintype "passive"))
    )
    (net (code "30") (name "/OUT_CAM0_TRIGGER_3V3") (class "Default")
      (node (ref "IC2") (pin "4") (pinfunction "O_4") (pintype "tri_state"))
      (node (ref "U2") (pin "3") (pinfunction "1Y_3") (pintype "bidirectional"))
      (node (ref "U5") (pin "2") (pinfunction "1A_2") (pintype "bidirectional"))
      (node (ref "X1") (pin "4") (pinfunction "4_4") (pintype "passive"))
    )
    (net (code "31") (name "/OUT_CAM0_TRIGGER_5V") (class "Default")
      (node (ref "U5") (pin "3") (pinfunction "1Y_3") (pintype "bidirectional"))
      (node (ref "X1") (pin "3") (pinfunction "3_3") (pintype "passive"))
    )
    (net (code "32") (name "/OUT_CAM1_TRIGGER_3V3") (class "Default")
      (node (ref "IC3") (pin "4") (pinfunction "O_4") (pintype "tri_state"))
      (node (ref "U2") (pin "6") (pinfunction "2Y_6") (pintype "bidirectional"))
      (node (ref "U5") (pin "5") (pinfunction "2A_5") (pintype "bidirectional"))
      (node (ref "X2") (pin "4") (pinfunction "4_4") (pintype "passive"))
    )
    (net (code "33") (name "/OUT_CAM1_TRIGGER_5V") (class "Default")
      (node (ref "U5") (pin "6") (pinfunction "2Y_6") (pintype "bidirectional"))
      (node (ref "X2") (pin "3") (pinfunction "3_3") (pintype "passive"))
    )
    (net (code "34") (name "/PDI_CLK") (class "Default")
      (node (ref "C37") (pin "1") (pinfunction "1_1") (pintype "passive"))
      (node (ref "IC6") (pin "35") (pinfunction "RESET/PDI-CLK_35") (pintype "input"))
      (node (ref "R34") (pin "1") (pinfunction "1_1") (pintype "passive"))
      (node (ref "SV1") (pin "5") (pinfunction "5_5") (pintype "passive"))
    )
    (net (code "35") (name "/PDI_DATA") (class "Default")
      (node (ref "IC6") (pin "34") (pinfunction "PDI-DATA_34") (pintype "bidirectional"))
      (node (ref "SV1") (pin "1") (pinfunction "1_1") (pintype "passive"))
    )
    (net (code "36") (name "/U_CAM0_TRIGGER_INV_ENBL") (class "Default")
      (node (ref "IC2") (pin "1") (pinfunction "OE_1") (pintype "input"))
      (node (ref "IC6") (pin "43") (pinfunction "PA3/ADC3_43") (pintype "bidirectional"))
      (node (ref "R6") (pin "2") (pinfunction "2_2") (pintype "passive"))
    )
    (net (code "37") (name "/U_CAM0_TRIGGER_N-INV-ENBL") (class "Default")
      (node (ref "IC6") (pin "44") (pinfunction "PA4/ADC4_44") (pintype "bidirectional"))
      (node (ref "R4") (pin "2") (pinfunction "2_2") (pintype "passive"))
      (node (ref "U2") (pin "1") (pinfunction "~{1OE}_1") (pintype "bidirectional"))
    )
    (net (code "38") (name "/U_CAM0_TRIGGER_TO_OUT0_BNC_ENBL") (class "Default")
      (node (ref "IC6") (pin "4") (pinfunction "PB0/ADC8/AREF_4") (pintype "bidirectional"))
      (node (ref "U4") (pin "10") (pinfunction "~{3OE}_10") (pintype "bidirectional"))
    )
    (net (code "39") (name "/U_CAM1_TRIGGER_INV_ENBL") (class "Default")
      (node (ref "IC3") (pin "1") (pinfunction "OE_1") (pintype "input"))
      (node (ref "IC6") (pin "14") (pinfunction "PC4/OC1A/#SS_14") (pintype "bidirectional"))
      (node (ref "R7") (pin "2") (pinfunction "2_2") (pintype "passive"))
    )
    (net (code "40") (name "/U_CAM1_TRIGGER_N-INV_ENBL") (class "Default")
      (node (ref "IC6") (pin "15") (pinfunction "PC5/OC1B/MOSI/XCK1_15") (pintype "bidirectional"))
      (node (ref "R2") (pin "2") (pinfunction "2_2") (pintype "passive"))
      (node (ref "U2") (pin "4") (pinfunction "~{2OE}_4") (pintype "bidirectional"))
    )
    (net (code "41") (name "/U_CAM1_TRIGGER_TO_OUT1_BNC_ENBL") (class "Default")
      (node (ref "IC6") (pin "5") (pinfunction "PB1/ADC9_5") (pintype "bidirectional"))
      (node (ref "U4") (pin "13") (pinfunction "~{4OE}_13") (pintype "bidirectional"))
    )
    (net (code "42") (name "/U_IN0_BNC_5V") (class "Default")
      (node (ref "IC6") (pin "7") (pinfunction "PB3/ADC11/DAC1_7") (pintype "bidirectional"))
      (node (ref "U2") (pin "11") (pinfunction "4Y_11") (pintype "bidirectional"))
    )
    (net (code "43") (name "/U_IN0_TO_CAM0_TRIGGER_ENBL") (class "Default")
      (node (ref "IC6") (pin "1") (pinfunction "PA5/ADC5_1") (pintype "bidirectional"))
      (node (ref "U4") (pin "1") (pinfunction "~{1OE}_1") (pintype "bidirectional"))
    )
    (net (code "44") (name "/U_IN0_TO_CAM1_TRIGGER_ENBL") (class "Default")
      (node (ref "IC6") (pin "2") (pinfunction "PA6/ADC6_2") (pintype "bidirectional"))
      (node (ref "U4") (pin "4") (pinfunction "~{2OE}_4") (pintype "bidirectional"))
    )
    (net (code "45") (name "/U_IN_CAM1_STROBE_5V") (class "Default")
      (node (ref "IC6") (pin "40") (pinfunction "PA0/ADC0/AREF_40") (pintype "bidirectional"))
      (node (ref "U3") (pin "3") (pinfunction "1Y_3") (pintype "bidirectional"))
    )
    (net (code "46") (name "/U_IN_CAM1_STROBE_PULLUP_5V") (class "Default")
      (node (ref "IC6") (pin "41") (pinfunction "PA1/ADC1_41") (pintype "bidirectional"))
      (node (ref "U3") (pin "6") (pinfunction "2Y_6") (pintype "bidirectional"))
    )
    (net (code "47") (name "/U_IN_CAM2_STROBE_5V") (class "Default")
      (node (ref "IC6") (pin "27") (pinfunction "~~{TXD1SCKCLKOPD7}_27") (pintype "bidirectional"))
      (node (ref "U3") (pin "8") (pinfunction "3Y_8") (pintype "bidirectional"))
    )
    (net (code "48") (name "/U_IN_CAM2_STROBE_PULLUP_5V") (class "Default")
      (node (ref "IC6") (pin "26") (pinfunction "~RXD1MISOPD6_26") (pintype "bidirectional"))
      (node (ref "U3") (pin "11") (pinfunction "4Y_11") (pintype "bidirectional"))
    )
    (net (code "49") (name "/U_IO_CAM0_TRIGGER") (class "Default")
      (node (ref "IC2") (pin "2") (pinfunction "I_2") (pintype "input"))
      (node (ref "IC6") (pin "20") (pinfunction "~{OC0APD0}_20") (pintype "bidirectional"))
      (node (ref "R3") (pin "2") (pinfunction "2_2") (pintype "passive"))
      (node (ref "U2") (pin "2") (pinfunction "1A_2") (pintype "bidirectional"))
      (node (ref "U4") (pin "3") (pinfunction "1Y_3") (pintype "bidirectional"))
      (node (ref "U4") (pin "9") (pinfunction "3A_9") (pintype "bidirectional"))
    )
    (net (code "50") (name "/U_IO_CAM1_TRIGGER") (class "Default")
      (node (ref "IC3") (pin "2") (pinfunction "I_2") (pintype "input"))
      (node (ref "IC6") (pin "10") (pinfunction "PC0/OC0A/SDA_10") (pintype "bidirectional"))
      (node (ref "R5") (pin "2") (pinfunction "2_2") (pintype "passive"))
      (node (ref "U2") (pin "5") (pinfunction "2A_5") (pintype "bidirectional"))
      (node (ref "U4") (pin "12") (pinfunction "4A_12") (pintype "bidirectional"))
      (node (ref "U4") (pin "6") (pinfunction "2Y_6") (pintype "bidirectional"))
    )
    (net (code "51") (name "/U_OUT0_BNC_5V") (class "Default")
      (node (ref "IC6") (pin "21") (pinfunction "~OC0BXCK0PD1_21") (pintype "bidirectional"))
      (node (ref "R10") (pin "1") (pinfunction "1_1") (pintype "passive"))
      (node (ref "U4") (pin "8") (pinfunction "3Y_8") (pintype "bidirectional"))
      (node (ref "U5") (pin "9") (pinfunction "3A_9") (pintype "bidirectional"))
    )
    (net (code "52") (name "/U_OUT1_BNC_5V") (class "Default")
      (node (ref "IC6") (pin "11") (pinfunction "PC1/OC0B/XCK0/SCL_11") (pintype "bidirectional"))
      (node (ref "R11") (pin "1") (pinfunction "1_1") (pintype "passive"))
      (node (ref "U4") (pin "11") (pinfunction "4Y_11") (pintype "bidirectional"))
      (node (ref "U5") (pin "12") (pinfunction "4A_12") (pintype "bidirectional"))
    )
    (net (code "53") (name "/VREF") (class "Default")
      (node (ref "R12") (pin "1") (pinfunction "1_1") (pintype "passive"))
      (node (ref "R13") (pin "2") (pinfunction "2_2") (pintype "passive"))
      (node (ref "U1") (pin "12") (pinfunction "FB_12") (pintype "bidirectional"))
    )
    (net (code "54") (name "GND") (class "Default")
      (node (ref "C1") (pin "2") (pinfunction "2_2") (pintype "passive"))
      (node (ref "C10") (pin "2") (pinfunction "2_2") (pintype "passive"))
      (node (ref "C12") (pin "2") (pinfunction "2_2") (pintype "passive"))
      (node (ref "C13") (pin "2") (pinfunction "2_2") (pintype "passive"))
      (node (ref "C14") (pin "2") (pinfunction "2_2") (pintype "passive"))
      (node (ref "C15") (pin "2") (pinfunction "2_2") (pintype "passive"))
      (node (ref "C16") (pin "2") (pinfunction "2_2") (pintype "passive"))
      (node (ref "C17") (pin "-") (pinfunction "-_-") (pintype "passive"))
      (node (ref "C18") (pin "2") (pinfunction "2_2") (pintype "passive"))
      (node (ref "C19") (pin "2") (pinfunction "2_2") (pintype "passive"))
      (node (ref "C2") (pin "2") (pinfunction "2_2") (pintype "passive"))
      (node (ref "C20") (pin "2") (pinfunction "2_2") (pintype "passive"))
      (node (ref "C21") (pin "2") (pinfunction "2_2") (pintype "passive"))
      (node (ref "C22") (pin "2") (pinfunction "2_2") (pintype "passive"))
      (node (ref "C23") (pin "2") (pinfunction "2_2") (pintype "passive"))
      (node (ref "C24") (pin "2") (pinfunction "2_2") (pintype "passive"))
      (node (ref "C25") (pin "2") (pinfunction "2_2") (pintype "passive"))
      (node (ref "C26") (pin "2") (pinfunction "2_2") (pintype "passive"))
      (node (ref "C27") (pin "2") (pinfunction "2_2") (pintype "passive"))
      (node (ref "C28") (pin "2") (pinfunction "2_2") (pintype "passive"))
      (node (ref "C29") (pin "2") (pinfunction "2_2") (pintype "passive"))
      (node (ref "C3") (pin "2") (pinfunction "2_2") (pintype "passive"))
      (node (ref "C30") (pin "2") (pinfunction "2_2") (pintype "passive"))
      (node (ref "C31") (pin "2") (pinfunction "2_2") (pintype "passive"))
      (node (ref "C32") (pin "2") (pinfunction "2_2") (pintype "passive"))
      (node (ref "C33") (pin "2") (pinfunction "2_2") (pintype "passive"))
      (node (ref "C34") (pin "2") (pinfunction "2_2") (pintype "passive"))
      (node (ref "C35") (pin "2") (pinfunction "2_2") (pintype "passive"))
      (node (ref "C36") (pin "2") (pinfunction "2_2") (pintype "passive"))
      (node (ref "C37") (pin "2") (pinfunction "2_2") (pintype "passive"))
      (node (ref "C4") (pin "2") (pinfunction "2_2") (pintype "passive"))
      (node (ref "C5") (pin "2") (pinfunction "2_2") (pintype "passive"))
      (node (ref "C6") (pin "2") (pinfunction "2_2") (pintype "passive"))
      (node (ref "C7") (pin "-") (pinfunction "-_-") (pintype "passive"))
      (node (ref "C8") (pin "2") (pinfunction "2_2") (pintype "passive"))
      (node (ref "C9") (pin "2") (pinfunction "2_2") (pintype "passive"))
      (node (ref "CLOCK_IN") (pin "5") (pinfunction "5_5") (pintype "passive"))
      (node (ref "D1") (pin "A") (pinfunction "A_A") (pintype "passive"))
      (node (ref "GND1_TP") (pin "TP") (pinfunction "TP_TP") (pintype "input"))
      (node (ref "GND2_TP") (pin "TP") (pinfunction "TP_TP") (pintype "input"))
      (node (ref "IC1") (pin "P$2") (pinfunction "GND_P$2") (pintype "bidirectional"))
      (node (ref "IC10") (pin "4") (pinfunction "AGND_4") (pintype "bidirectional"))
      (node (ref "IC2") (pin "3") (pinfunction "GND_3") (pintype "power_in"))
      (node (ref "IC3") (pin "3") (pinfunction "GND_3") (pintype "power_in"))
      (node (ref "IC4") (pin "18") (pinfunction "GND_18") (pintype "power_in"))
      (node (ref "IC4") (pin "21") (pinfunction "GND_21") (pintype "power_in"))
      (node (ref "IC4") (pin "25") (pinfunction "GND_25") (pintype "power_in"))
      (node (ref "IC4") (pin "26") (pinfunction "TEST_26") (pintype "input"))
      (node (ref "IC4") (pin "7") (pinfunction "GND_7") (pintype "power_in"))
      (node (ref "IC5") (pin "2") (pinfunction "GND_2") (pintype "bidirectional"))
      (node (ref "IC6") (pin "18") (pinfunction "GND_18") (pintype "power_in"))
      (node (ref "IC6") (pin "30") (pinfunction "GND_30") (pintype "power_in"))
      (node (ref "IC6") (pin "38") (pinfunction "GND_38") (pintype "power_in"))
      (node (ref "IC6") (pin "8") (pinfunction "GND_8") (pintype "power_in"))
      (node (ref "IC7") (pin "3") (pinfunction "GND_3") (pintype "power_in"))
      (node (ref "IC8") (pin "3") (pinfunction "GND_3") (pintype "power_in"))
      (node (ref "IC9") (pin "2") (pinfunction "GND_2") (pintype "bidirectional"))
      (node (ref "OSC1") (pin "P$2") (pinfunction "GND_P$2") (pintype "passive"))
      (node (ref "PWR1") (pin "P2") (pinfunction "2_P2") (pintype "passive"))
      (node (ref "PWR1") (pin "P3") (pinfunction "3_P3") (pintype "passive"))
      (node (ref "R1") (pin "2") (pinfunction "2_2") (pintype "passive"))
      (node (ref "R10") (pin "2") (pinfunction "2_2") (pintype "passive"))
      (node (ref "R11") (pin "2") (pinfunction "2_2") (pintype "passive"))
      (node (ref "R13") (pin "1") (pinfunction "1_1") (pintype "passive"))
      (node (ref "R15") (pin "1") (pinfunction "1_1") (pintype "passive"))
      (node (ref "R17") (pin "1") (pinfunction "1_1") (pintype "passive"))
      (node (ref "R2") (pin "1") (pinfunction "1_1") (pintype "passive"))
      (node (ref "R21") (pin "1") (pinfunction "1_1") (pintype "passive"))
      (node (ref "R22") (pin "2") (pinfunction "2_2") (pintype "passive"))
      (node (ref "R23") (pin "2") (pinfunction "2_2") (pintype "passive"))
      (node (ref "R3") (pin "1") (pinfunction "1_1") (pintype "passive"))
      (node (ref "R32") (pin "2") (pinfunction "2_2") (pintype "passive"))
      (node (ref "R4") (pin "1") (pinfunction "1_1") (pintype "passive"))
      (node (ref "R5") (pin "1") (pinfunction "1_1") (pintype "passive"))
      (node (ref "SV1") (pin "6") (pinfunction "6_6") (pintype "passive"))
      (node (ref "T1") (pin "2") (pinfunction "E_2") (pintype "passive"))
      (node (ref "T2") (pin "2") (pinfunction "E_2") (pintype "passive"))
      (node (ref "T3") (pin "2") (pinfunction "E_2") (pintype "passive"))
      (node (ref "T4") (pin "2") (pinfunction "E_2") (pintype "passive"))
      (node (ref "U1") (pin "1") (pinfunction "GND_1") (pintype "bidirectional"))
      (node (ref "U1") (pin "14") (pinfunction "SYNC_14") (pintype "bidirectional"))
      (node (ref "U1") (pin "16") (pinfunction "GND_16") (pintype "bidirectional"))
      (node (ref "U1") (pin "17") (pinfunction "GND_17") (pintype "bidirectional"))
      (node (ref "U1") (pin "8") (pinfunction "GND_8") (pintype "bidirectional"))
      (node (ref "U1") (pin "9") (pinfunction "GND_9") (pintype "bidirectional"))
      (node (ref "U2") (pin "10") (pinfunction "~{3OE}_10") (pintype "bidirectional"))
      (node (ref "U2") (pin "7") (pinfunction "GND_7") (pintype "bidirectional"))
      (node (ref "U3") (pin "7") (pinfunction "GND_7") (pintype "bidirectional"))
      (node (ref "U4") (pin "7") (pinfunction "GND_7") (pintype "bidirectional"))
      (node (ref "U5") (pin "1") (pinfunction "~{1OE}_1") (pintype "bidirectional"))
      (node (ref "U5") (pin "10") (pinfunction "~{3OE}_10") (pintype "bidirectional"))
      (node (ref "U5") (pin "13") (pinfunction "~{4OE}_13") (pintype "bidirectional"))
      (node (ref "U5") (pin "4") (pinfunction "~{2OE}_4") (pintype "bidirectional"))
      (node (ref "U5") (pin "7") (pinfunction "GND_7") (pintype "bidirectional"))
      (node (ref "USB1") (pin "P$5") (pinfunction "5_P$5") (pintype "bidirectional"))
      (node (ref "X1") (pin "2") (pinfunction "2_2") (pintype "passive"))
      (node (ref "X1") (pin "7") (pinfunction "7_7") (pintype "passive"))
      (node (ref "X2") (pin "2") (pinfunction "2_2") (pintype "passive"))
      (node (ref "X2") (pin "7") (pinfunction "7_7") (pintype "passive"))
      (node (ref "X3") (pin "2") (pinfunction "2_2") (pintype "passive"))
      (node (ref "X3") (pin "3") (pinfunction "2_3") (pintype "passive"))
      (node (ref "X4") (pin "2") (pinfunction "2_2") (pintype "passive"))
      (node (ref "X4") (pin "3") (pinfunction "2_3") (pintype "passive"))
      (node (ref "X5") (pin "2") (pinfunction "2_2") (pintype "passive"))
      (node (ref "X5") (pin "3") (pinfunction "2_3") (pintype "passive"))
    )
    (net (code "55") (name "Net-(C11-Pad2)") (class "Default")
      (node (ref "C11") (pin "2") (pinfunction "2_2") (pintype "passive"))
      (node (ref "D1") (pin "C") (pinfunction "C_C") (pintype "passive"))
      (node (ref "L1") (pin "2") (pinfunction "2_2") (pintype "passive"))
      (node (ref "U1") (pin "5") (pinfunction "SW_5") (pintype "bidirectional"))
      (node (ref "U1") (pin "6") (pinfunction "SW_6") (pintype "bidirectional"))
    )
    (net (code "56") (name "Net-(CLOCK_IN-Pad1)") (class "Default")
      (node (ref "CLOCK_IN") (pin "1") (pinfunction "1_1") (pintype "passive"))
      (node (ref "R35") (pin "2") (pinfunction "2_2") (pintype "passive"))
      (node (ref "R36") (pin "1") (pinfunction "1_1") (pintype "passive"))
    )
    (net (code "57") (name "Net-(IC4-3V3OUT)") (class "Default")
      (node (ref "C14") (pin "1") (pinfunction "1_1") (pintype "passive"))
      (node (ref "IC4") (pin "17") (pinfunction "3V3OUT_17") (pintype "output"))
    )
    (net (code "58") (name "Net-(IC4-USBDM)") (class "Default")
      (node (ref "C13") (pin "1") (pinfunction "1_1") (pintype "passive"))
      (node (ref "IC1") (pin "P$6") (pinfunction "IO1_P$6") (pintype "bidirectional"))
      (node (ref "IC4") (pin "16") (pinfunction "USBDM_16") (pintype "bidirectional"))
    )
    (net (code "59") (name "Net-(IC4-USBDP)") (class "Default")
      (node (ref "C10") (pin "1") (pinfunction "1_1") (pintype "passive"))
      (node (ref "IC1") (pin "P$4") (pinfunction "IO2_P$4") (pintype "bidirectional"))
      (node (ref "IC4") (pin "15") (pinfunction "USBDP_15") (pintype "bidirectional"))
    )
    (net (code "60") (name "Net-(IC6-PR1{slash}XTAL1)") (class "Default")
      (node (ref "IC6") (pin "37") (pinfunction "PR1/XTAL1_37") (pintype "bidirectional"))
      (node (ref "OSC1") (pin "P$3") (pinfunction "OUTPUT_P$3") (pintype "passive"))
    )
    (net (code "61") (name "Net-(IC9-OUT)") (class "Default")
      (node (ref "C35") (pin "1") (pinfunction "1_1") (pintype "passive"))
      (node (ref "C36") (pin "1") (pinfunction "1_1") (pintype "passive"))
      (node (ref "IC9") (pin "5") (pinfunction "OUT_5") (pintype "bidirectional"))
      (node (ref "R35") (pin "1") (pinfunction "1_1") (pintype "passive"))
    )
    (net (code "62") (name "Net-(IC10-A1)") (class "Default")
      (node (ref "IC10") (pin "2") (pinfunction "A1_2") (pintype "bidirectional"))
      (node (ref "IC7") (pin "4") (pinfunction "O_4") (pintype "tri_state"))
      (node (ref "IC8") (pin "4") (pinfunction "O_4") (pintype "tri_state"))
    )
    (net (code "63") (name "Net-(IC10-B1)") (class "Default")
      (node (ref "CLOCK_OUT") (pin "4") (pinfunction "4_4") (pintype "passive"))
      (node (ref "IC10") (pin "6") (pinfunction "B1_6") (pintype "bidirectional"))
    )
    (net (code "64") (name "Net-(IC10-BGND)") (class "Default")
      (node (ref "C38") (pin "2") (pinfunction "2_2") (pintype "passive"))
      (node (ref "CLOCK_OUT") (pin "5") (pinfunction "5_5") (pintype "passive"))
      (node (ref "IC10") (pin "5") (pinfunction "BGND_5") (pintype "bidirectional"))
    )
    (net (code "65") (name "Net-(IC10-BVDD)") (class "Default")
      (node (ref "C38") (pin "1") (pinfunction "1_1") (pintype "passive"))
      (node (ref "CLOCK_OUT") (pin "1") (pinfunction "1_1") (pintype "passive"))
      (node (ref "IC10") (pin "8") (pinfunction "BVDD_8") (pintype "bidirectional"))
    )
    (net (code "66") (name "Net-(LED1A-C)") (class "Default")
      (node (ref "LED1") (pin "C1") (pinfunction "C_C1") (pintype "passive"))
      (node (ref "R27") (pin "1") (pinfunction "1_1") (pintype "passive"))
    )
    (net (code "67") (name "Net-(LED1B-C)") (class "Default")
      (node (ref "LED1") (pin "C2") (pinfunction "C_C2") (pintype "passive"))
      (node (ref "R26") (pin "1") (pinfunction "1_1") (pintype "passive"))
    )
    (net (code "68") (name "Net-(LED2A-C)") (class "Default")
      (node (ref "LED2") (pin "C1") (pinfunction "C_C1") (pintype "passive"))
      (node (ref "R31") (pin "1") (pinfunction "1_1") (pintype "passive"))
    )
    (net (code "69") (name "Net-(LED2B-C)") (class "Default")
      (node (ref "LED2") (pin "C2") (pinfunction "C_C2") (pintype "passive"))
      (node (ref "R30") (pin "1") (pinfunction "1_1") (pintype "passive"))
    )
    (net (code "70") (name "Net-(T1-B)") (class "Default")
      (node (ref "R24") (pin "2") (pinfunction "2_2") (pintype "passive"))
      (node (ref "T1") (pin "1") (pinfunction "B_1") (pintype "passive"))
    )
    (net (code "71") (name "Net-(T1-C)") (class "Default")
      (node (ref "R26") (pin "2") (pinfunction "2_2") (pintype "passive"))
      (node (ref "T1") (pin "3") (pinfunction "C_3") (pintype "passive"))
    )
    (net (code "72") (name "Net-(T2-B)") (class "Default")
      (node (ref "R25") (pin "2") (pinfunction "2_2") (pintype "passive"))
      (node (ref "T2") (pin "1") (pinfunction "B_1") (pintype "passive"))
    )
    (net (code "73") (name "Net-(T2-C)") (class "Default")
      (node (ref "R27") (pin "2") (pinfunction "2_2") (pintype "passive"))
      (node (ref "T2") (pin "3") (pinfunction "C_3") (pintype "passive"))
    )
    (net (code "74") (name "Net-(T3-B)") (class "Default")
      (node (ref "R28") (pin "2") (pinfunction "2_2") (pintype "passive"))
      (node (ref "T3") (pin "1") (pinfunction "B_1") (pintype "passive"))
    )
    (net (code "75") (name "Net-(T3-C)") (class "Default")
      (node (ref "R30") (pin "2") (pinfunction "2_2") (pintype "passive"))
      (node (ref "T3") (pin "3") (pinfunction "C_3") (pintype "passive"))
    )
    (net (code "76") (name "Net-(T4-B)") (class "Default")
      (node (ref "R29") (pin "2") (pinfunction "2_2") (pintype "passive"))
      (node (ref "T4") (pin "1") (pinfunction "B_1") (pintype "passive"))
    )
    (net (code "77") (name "Net-(T4-C)") (class "Default")
      (node (ref "R31") (pin "2") (pinfunction "2_2") (pintype "passive"))
      (node (ref "T4") (pin "3") (pinfunction "C_3") (pintype "passive"))
    )
    (net (code "78") (name "Net-(U1-BOOST)") (class "Default")
      (node (ref "C11") (pin "1") (pinfunction "1_1") (pintype "passive"))
      (node (ref "D2") (pin "C") (pinfunction "C_C") (pintype "passive"))
      (node (ref "U1") (pin "2") (pinfunction "BOOST_2") (pintype "bidirectional"))
    )
    (net (code "79") (name "Net-(USB1-2)") (class "Default")
      (node (ref "IC1") (pin "P$1") (pinfunction "IO1_P$1") (pintype "bidirectional"))
      (node (ref "USB1") (pin "P$2") (pinfunction "2_P$2") (pintype "bidirectional"))
    )
    (net (code "80") (name "Net-(USB1-3)") (class "Default")
      (node (ref "IC1") (pin "P$3") (pinfunction "IO2_P$3") (pintype "bidirectional"))
      (node (ref "USB1") (pin "P$3") (pinfunction "3_P$3") (pintype "bidirectional"))
    )
    (net (code "81") (name "Net-(USB1-P$1)") (class "Default")
      (node (ref "R1") (pin "1") (pinfunction "1_1") (pintype "passive"))
      (node (ref "USB1") (pin "SHIELD_1") (pinfunction "P$1_SHIELD_1") (pintype "bidirectional"))
    )
    (net (code "82") (name "Net-(USB1-P$4)") (class "Default")
      (node (ref "C1") (pin "1") (pinfunction "1_1") (pintype "passive"))
      (node (ref "USB1") (pin "SHIELD_4") (pinfunction "P$4_SHIELD_4") (pintype "bidirectional"))
    )
    (net (code "83") (name "V+") (class "Default")
      (node (ref "C17") (pin "+") (pinfunction "+_+") (pintype "passive"))
      (node (ref "C18") (pin "1") (pinfunction "1_1") (pintype "passive"))
      (node (ref "D2") (pin "A") (pinfunction "A_A") (pintype "passive"))
      (node (ref "L1") (pin "1") (pinfunction "1_1") (pintype "passive"))
      (node (ref "R12") (pin "2") (pinfunction "2_2") (pintype "passive"))
      (node (ref "X1") (pin "8") (pinfunction "8_8") (pintype "passive"))
      (node (ref "X2") (pin "8") (pinfunction "8_8") (pintype "passive"))
    )
    (net (code "84") (name "unconnected-(IC4-CBUS0-Pad23)") (class "Default")
      (node (ref "IC4") (pin "23") (pinfunction "CBUS0_23") (pintype "passive"))
    )
    (net (code "85") (name "unconnected-(IC4-CBUS1-Pad22)") (class "Default")
      (node (ref "IC4") (pin "22") (pinfunction "CBUS1_22") (pintype "passive"))
    )
    (net (code "86") (name "unconnected-(IC4-CBUS2-Pad13)") (class "Default")
      (node (ref "IC4") (pin "13") (pinfunction "CBUS2_13") (pintype "passive"))
    )
    (net (code "87") (name "unconnected-(IC4-CBUS3-Pad14)") (class "Default")
      (node (ref "IC4") (pin "14") (pinfunction "CBUS3_14") (pintype "passive"))
    )
    (net (code "88") (name "unconnected-(IC4-CBUS4-Pad12)") (class "Default")
      (node (ref "IC4") (pin "12") (pinfunction "CBUS4_12") (pintype "passive"))
    )
    (net (code "89") (name "unconnected-(IC4-OSCI-Pad27)") (class "Default")
      (node (ref "IC4") (pin "27") (pinfunction "OSCI_27") (pintype "passive"))
    )
    (net (code "90") (name "unconnected-(IC4-OSCO-Pad28)") (class "Default")
      (node (ref "IC4") (pin "28") (pinfunction "OSCO_28") (pintype "output"))
    )
    (net (code "91") (name "unconnected-(IC4-~{DCD}-Pad10)") (class "Default")
      (node (ref "IC4") (pin "10") (pinfunction "~{DCD}_10") (pintype "passive"))
    )
    (net (code "92") (name "unconnected-(IC4-~{DSR}-Pad9)") (class "Default")
      (node (ref "IC4") (pin "9") (pinfunction "~{DSR}_9") (pintype "passive"))
    )
    (net (code "93") (name "unconnected-(IC4-~{DTR}-Pad2)") (class "Default")
      (node (ref "IC4") (pin "2") (pinfunction "~{DTR}_2") (pintype "passive"))
    )
    (net (code "94") (name "unconnected-(IC4-~{RESET}-Pad19)") (class "Default")
      (node (ref "IC4") (pin "19") (pinfunction "~{RESET}_19") (pintype "passive"))
    )
    (net (code "95") (name "unconnected-(IC4-~{RI}-Pad6)") (class "Default")
      (node (ref "IC4") (pin "6") (pinfunction "~{RI}_6") (pintype "passive"))
    )
    (net (code "96") (name "unconnected-(IC5-N{slash}C-Pad4)") (class "Default")
      (node (ref "IC5") (pin "4") (pinfunction "N/C_4") (pintype "bidirectional"))
    )
    (net (code "97") (name "unconnected-(IC6-PA2{slash}ADC2-Pad42)") (class "Default")
      (node (ref "IC6") (pin "42") (pinfunction "PA2/ADC2_42") (pintype "bidirectional"))
    )
    (net (code "98") (name "unconnected-(IC6-PC6{slash}MISO{slash}RXD1-Pad16)") (class "Default")
      (node (ref "IC6") (pin "16") (pinfunction "PC6/MISO/RXD1_16") (pintype "bidirectional"))
    )
    (net (code "99") (name "unconnected-(IC9-N{slash}C-Pad4)") (class "Default")
      (node (ref "IC9") (pin "4") (pinfunction "N/C_4") (pintype "bidirectional"))
    )
    (net (code "100") (name "unconnected-(IC10-AVDD{slash}NC-Pad3)") (class "Default")
      (node (ref "IC10") (pin "3") (pinfunction "AVDD/NC_3") (pintype "bidirectional"))
    )
    (net (code "101") (name "unconnected-(IC10-BGND{slash}NC-Pad7)") (class "Default")
      (node (ref "IC10") (pin "7") (pinfunction "BGND/NC_7") (pintype "bidirectional"))
    )
    (net (code "102") (name "unconnected-(OSC1-STANDBY#-PadP$1)") (class "Default")
      (node (ref "OSC1") (pin "P$1") (pinfunction "STANDBY#_P$1") (pintype "passive"))
    )
    (net (code "103") (name "unconnected-(SV1-Pad3)") (class "Default")
      (node (ref "SV1") (pin "3") (pinfunction "3_3") (pintype "passive"))
    )
    (net (code "104") (name "unconnected-(SV1-Pad4)") (class "Default")
      (node (ref "SV1") (pin "4") (pinfunction "4_4") (pintype "passive"))
    )
    (net (code "105") (name "unconnected-(U1-NC7-Pad7)") (class "Default")
      (node (ref "U1") (pin "7") (pinfunction "NC7_7") (pintype "bidirectional"))
    )
    (net (code "106") (name "unconnected-(U1-NC10-Pad10)") (class "Default")
      (node (ref "U1") (pin "10") (pinfunction "NC10_10") (pintype "bidirectional"))
    )
    (net (code "107") (name "unconnected-(U1-NC15-Pad15)") (class "Default")
      (node (ref "U1") (pin "15") (pinfunction "NC15_15") (pintype "bidirectional"))
    )
    (net (code "108") (name "unconnected-(U1-VC-Pad13)") (class "Default")
      (node (ref "U1") (pin "13") (pinfunction "VC_13") (pintype "bidirectional"))
    )
    (net (code "109") (name "unconnected-(U1-~{SHDN}-Pad11)") (class "Default")
      (node (ref "U1") (pin "11") (pinfunction "~{SHDN}_11") (pintype "bidirectional"))
    )
    (net (code "110") (name "unconnected-(U2-3A-Pad9)") (class "Default")
      (node (ref "U2") (pin "9") (pinfunction "3A_9") (pintype "bidirectional"))
    )
    (net (code "111") (name "unconnected-(U2-3Y-Pad8)") (class "Default")
      (node (ref "U2") (pin "8") (pinfunction "3Y_8") (pintype "bidirectional"))
    )
    (net (code "112") (name "unconnected-(USB1-4-PadP$4)") (class "Default")
      (node (ref "USB1") (pin "P$4") (pinfunction "4_P$4") (pintype "bidirectional"))
    )
    (net (code "113") (name "unconnected-(USB1-P$2-PadSHIELD_2)") (class "Default")
      (node (ref "USB1") (pin "SHIELD_2") (pinfunction "P$2_SHIELD_2") (pintype "bidirectional"))
    )
    (net (code "114") (name "unconnected-(USB1-P$3-PadSHIELD_3)") (class "Default")
      (node (ref "USB1") (pin "SHIELD_3") (pinfunction "P$3_SHIELD_3") (pintype "bidirectional"))
    )
  )
)
